# schaltung_endstuffe.net
KiCad netlist of a schematic drawn in EAGLE
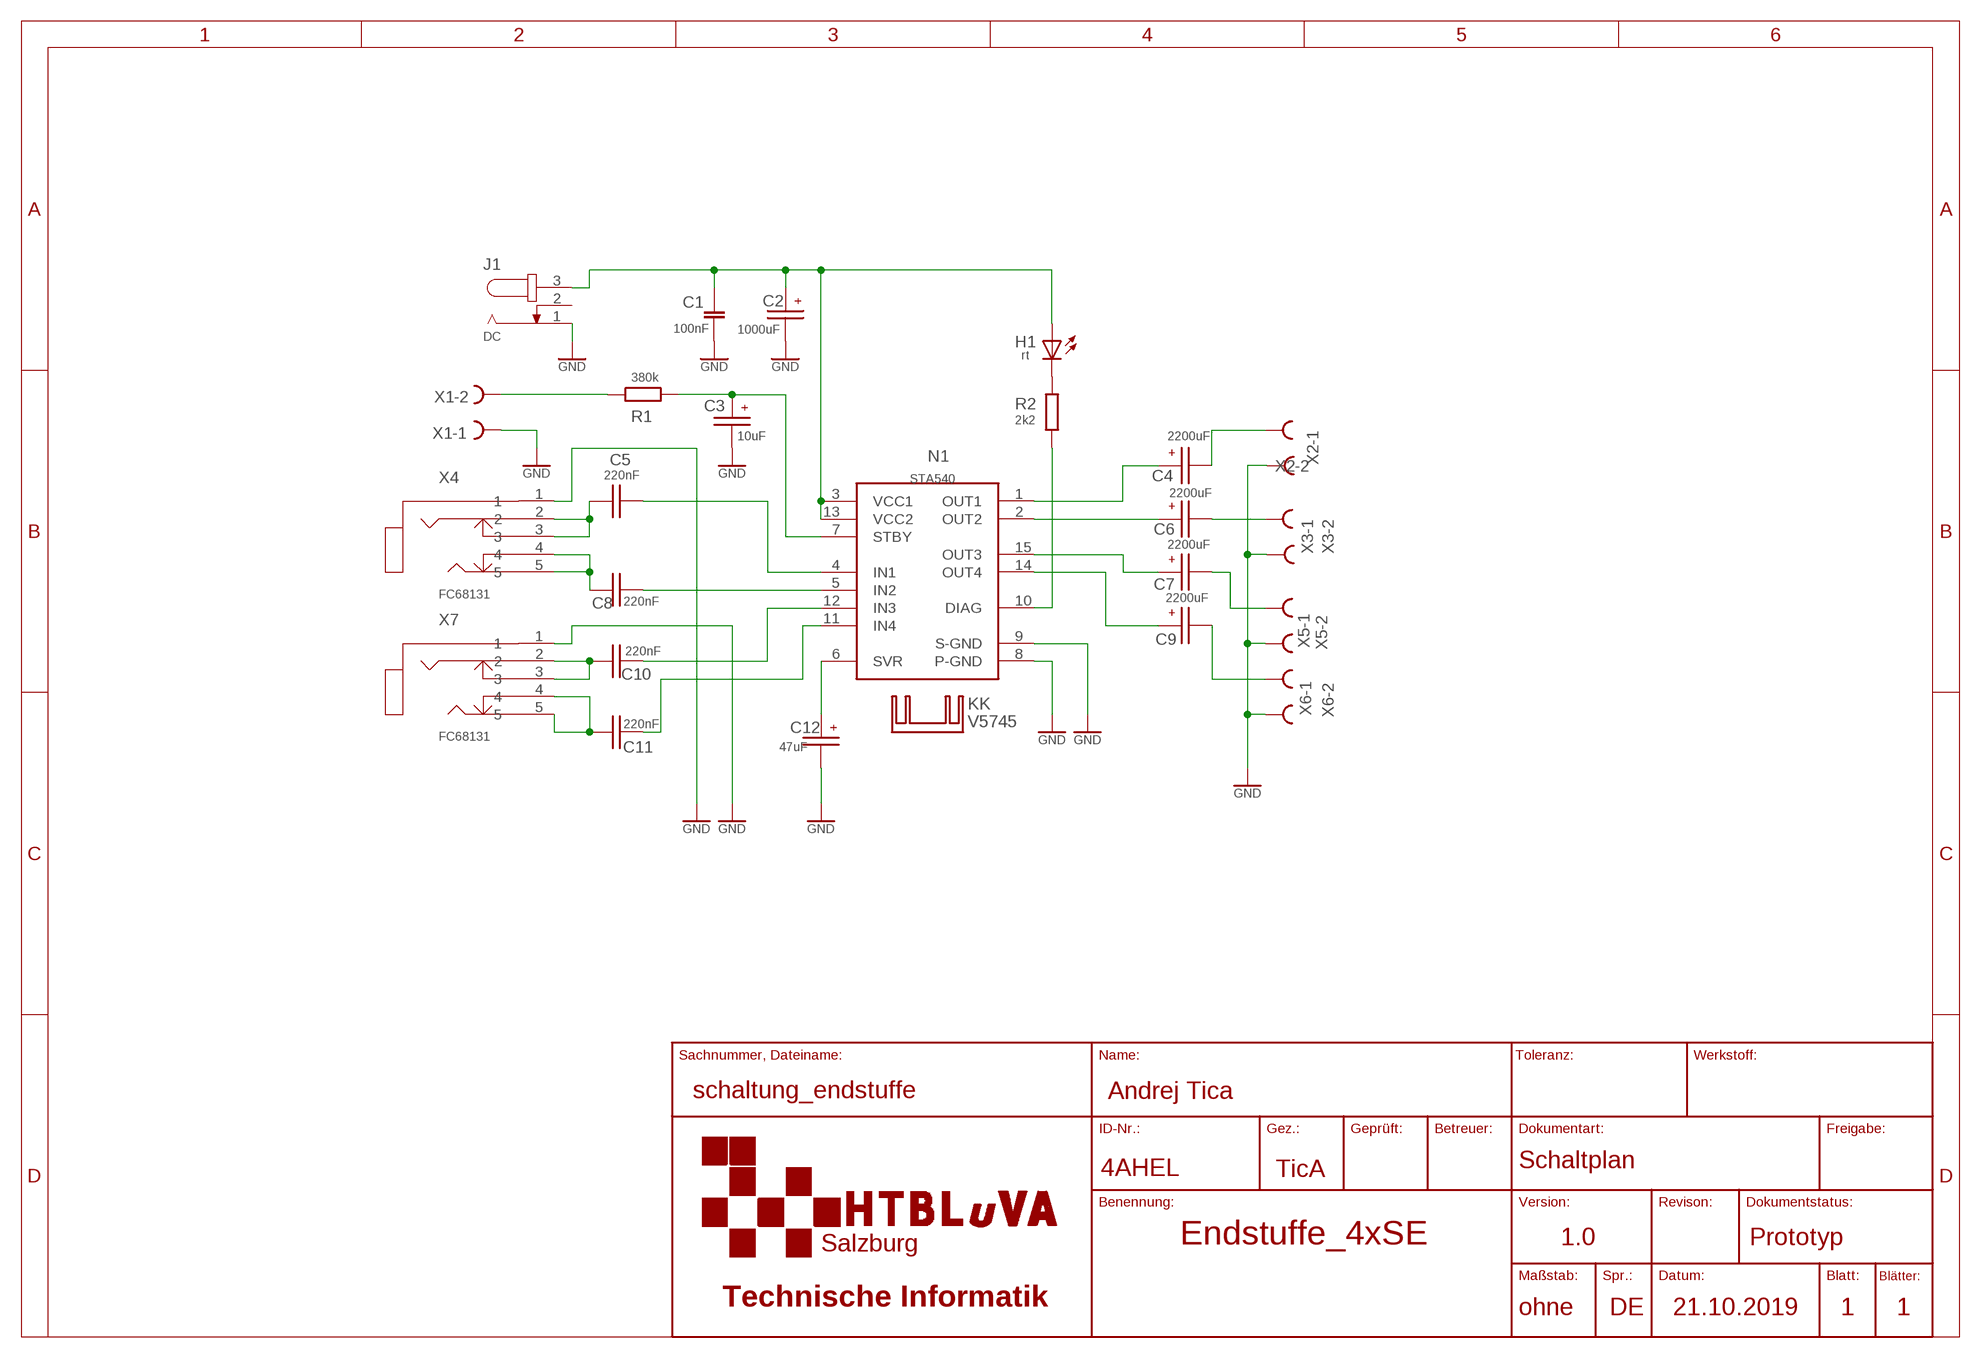
[diagram p0: schematic, sheet 1]

(export (version "E")
  (design (tool "Eeschema 10.0.6"))
  (components
    (comp (ref "C1")
      (value "100nF")
      (footprint "eagle-import:MYLIB_C1206")
      (libsource (lib "eagle-import") (part "C-EU1206"))
    )
    (comp (ref "C2")
      (value "1000uF")
      (footprint "eagle-import:E7,5-16")
      (libsource (lib "eagle-import") (part "CPOL-V_E7.5-16"))
    )
    (comp (ref "C3")
      (value "10uF")
      (footprint "eagle-import:E3,5-8")
      (libsource (lib "eagle-import") (part "CPOL-V_E3.5-8"))
    )
    (comp (ref "C4")
      (value "2200uF")
      (footprint "eagle-import:E7,5-16")
      (libsource (lib "eagle-import") (part "CPOL-V_E7.5-16"))
    )
    (comp (ref "C5")
      (value "220nF")
      (footprint "eagle-import:C050-025X075")
      (libsource (lib "eagle-import") (part "C-V_050-025X075"))
    )
    (comp (ref "C6")
      (value "2200uF")
      (footprint "eagle-import:E7,5-16")
      (libsource (lib "eagle-import") (part "CPOL-V_E7.5-16"))
    )
    (comp (ref "C7")
      (value "2200uF")
      (footprint "eagle-import:E7,5-16")
      (libsource (lib "eagle-import") (part "CPOL-V_E7.5-16"))
    )
    (comp (ref "C8")
      (value "220nF")
      (footprint "eagle-import:C050-025X075")
      (libsource (lib "eagle-import") (part "C-V_050-025X075"))
    )
    (comp (ref "C9")
      (value "2200uF")
      (footprint "eagle-import:E7,5-16")
      (libsource (lib "eagle-import") (part "CPOL-V_E7.5-16"))
    )
    (comp (ref "C10")
      (value "220nF")
      (footprint "eagle-import:C050-025X075")
      (libsource (lib "eagle-import") (part "C-V_050-025X075"))
    )
    (comp (ref "C11")
      (value "220nF")
      (footprint "eagle-import:C050-025X075")
      (libsource (lib "eagle-import") (part "C-V_050-025X075"))
    )
    (comp (ref "C12")
      (value "47uF")
      (footprint "eagle-import:E3,5-8")
      (libsource (lib "eagle-import") (part "CPOL-V_E3.5-8"))
    )
    (comp (ref "H1")
      (value "rt")
      (footprint "eagle-import:LED5MM")
      (libsource (lib "eagle-import") (part "LED_5MM"))
    )
    (comp (ref "J1")
      (value "DC")
      (footprint "eagle-import:SPC4077")
      (libsource (lib "eagle-import") (part "JACK-PLUG0"))
    )
    (comp (ref "KK")
      (value "V5745")
      (footprint "eagle-import:V5745")
      (libsource (lib "eagle-import") (part "V5745"))
    )
    (comp (ref "N1")
      (value "STA540")
      (footprint "eagle-import:MULTIWATT15")
      (fields (field (name "MF") "STMicroelectronics"))
      (libsource (lib "eagle-import") (part "STA540"))
    )
    (comp (ref "R1")
      (value "380k")
      (footprint "eagle-import:0204_7")
      (libsource (lib "eagle-import") (part "R-H_0204/7"))
    )
    (comp (ref "R2")
      (value "2k2")
      (footprint "eagle-import:0204_7")
      (libsource (lib "eagle-import") (part "R-H_0204/7"))
    )
    (comp (ref "X1")
      (value "AK500/2")
      (footprint "eagle-import:AK500_2")
      (libsource (lib "eagle-import") (part "AK500/2"))
    )
    (comp (ref "X2")
      (value "AK500/2")
      (footprint "eagle-import:AK500_2")
      (libsource (lib "eagle-import") (part "AK500/2"))
    )
    (comp (ref "X3")
      (value "AK500/2")
      (footprint "eagle-import:AK500_2")
      (libsource (lib "eagle-import") (part "AK500/2"))
    )
    (comp (ref "X4")
      (value "FC68131")
      (footprint "eagle-import:FC68131-5P")
      (fields (field (name "MF") "Cliff"))
      (libsource (lib "eagle-import") (part "FC68131"))
    )
    (comp (ref "X5")
      (value "AK500/2")
      (footprint "eagle-import:AK500_2")
      (libsource (lib "eagle-import") (part "AK500/2"))
    )
    (comp (ref "X6")
      (value "AK500/2")
      (footprint "eagle-import:AK500_2")
      (libsource (lib "eagle-import") (part "AK500/2"))
    )
    (comp (ref "X7")
      (value "FC68131")
      (footprint "eagle-import:FC68131-5P")
      (fields (field (name "MF") "Cliff"))
      (libsource (lib "eagle-import") (part "FC68131"))
    )
  )
  (nets
    (net (code "1") (name "GND") (class "Default")
      (node (ref "C1") (pin "+") (pinfunction "2_+") (pintype "passive"))
      (node (ref "C12") (pin "-") (pinfunction "-_-") (pintype "passive"))
      (node (ref "C2") (pin "-") (pinfunction "-_-") (pintype "passive"))
      (node (ref "C3") (pin "-") (pinfunction "-_-") (pintype "passive"))
      (node (ref "J1") (pin "1") (pinfunction "1_1") (pintype "passive"))
      (node (ref "N1") (pin "8") (pinfunction "P-GND_8") (pintype "bidirectional"))
      (node (ref "N1") (pin "9") (pinfunction "S-GND_9") (pintype "bidirectional"))
      (node (ref "X1") (pin "1") (pinfunction "KL_1") (pintype "passive"))
      (node (ref "X2") (pin "1") (pinfunction "KL_1") (pintype "passive"))
      (node (ref "X3") (pin "2") (pinfunction "KL_2") (pintype "passive"))
      (node (ref "X4") (pin "1") (pinfunction "1_1") (pintype "bidirectional"))
      (node (ref "X5") (pin "2") (pinfunction "KL_2") (pintype "passive"))
      (node (ref "X6") (pin "2") (pinfunction "KL_2") (pintype "passive"))
      (node (ref "X7") (pin "1") (pinfunction "1_1") (pintype "bidirectional"))
    )
    (net (code "2") (name "Net-(C1-1)") (class "Default")
      (node (ref "C1") (pin "-") (pinfunction "1_-") (pintype "passive"))
      (node (ref "C2") (pin "+") (pinfunction "+_+") (pintype "passive"))
      (node (ref "H1") (pin "A") (pinfunction "A_A") (pintype "passive"))
      (node (ref "J1") (pin "3") (pinfunction "3_3") (pintype "passive"))
      (node (ref "N1") (pin "13") (pinfunction "VCC2_13") (pintype "bidirectional"))
      (node (ref "N1") (pin "3") (pinfunction "VCC1_3") (pintype "bidirectional"))
    )
    (net (code "3") (name "Net-(C5-Pad1)") (class "Default")
      (node (ref "C5") (pin "1") (pinfunction "1_1") (pintype "passive"))
      (node (ref "X4") (pin "2") (pinfunction "2_2") (pintype "bidirectional"))
      (node (ref "X4") (pin "3") (pinfunction "3_3") (pintype "bidirectional"))
    )
    (net (code "4") (name "Net-(C8-Pad1)") (class "Default")
      (node (ref "C8") (pin "1") (pinfunction "1_1") (pintype "passive"))
      (node (ref "X4") (pin "4") (pinfunction "4_4") (pintype "bidirectional"))
      (node (ref "X4") (pin "5") (pinfunction "5_5") (pintype "bidirectional"))
    )
    (net (code "5") (name "Net-(C10-Pad1)") (class "Default")
      (node (ref "C10") (pin "1") (pinfunction "1_1") (pintype "passive"))
      (node (ref "X7") (pin "2") (pinfunction "2_2") (pintype "bidirectional"))
      (node (ref "X7") (pin "3") (pinfunction "3_3") (pintype "bidirectional"))
    )
    (net (code "6") (name "Net-(C11-Pad1)") (class "Default")
      (node (ref "C11") (pin "1") (pinfunction "1_1") (pintype "passive"))
      (node (ref "X7") (pin "4") (pinfunction "4_4") (pintype "bidirectional"))
      (node (ref "X7") (pin "5") (pinfunction "5_5") (pintype "bidirectional"))
    )
    (net (code "7") (name "Net-(H1-C)") (class "Default")
      (node (ref "H1") (pin "K") (pinfunction "C_K") (pintype "passive"))
      (node (ref "R2") (pin "2") (pinfunction "2_2") (pintype "passive"))
    )
    (net (code "8") (name "Net-(N1-DIAG)") (class "Default")
      (node (ref "N1") (pin "10") (pinfunction "DIAG_10") (pintype "bidirectional"))
      (node (ref "R2") (pin "1") (pinfunction "1_1") (pintype "passive"))
    )
    (net (code "9") (name "Net-(N1-IN1)") (class "Default")
      (node (ref "C5") (pin "2") (pinfunction "2_2") (pintype "passive"))
      (node (ref "N1") (pin "4") (pinfunction "IN1_4") (pintype "bidirectional"))
    )
    (net (code "10") (name "Net-(N1-IN2)") (class "Default")
      (node (ref "C8") (pin "2") (pinfunction "2_2") (pintype "passive"))
      (node (ref "N1") (pin "5") (pinfunction "IN2_5") (pintype "bidirectional"))
    )
    (net (code "11") (name "Net-(N1-IN3)") (class "Default")
      (node (ref "C10") (pin "2") (pinfunction "2_2") (pintype "passive"))
      (node (ref "N1") (pin "12") (pinfunction "IN3_12") (pintype "bidirectional"))
    )
    (net (code "12") (name "Net-(N1-IN4)") (class "Default")
      (node (ref "C11") (pin "2") (pinfunction "2_2") (pintype "passive"))
      (node (ref "N1") (pin "11") (pinfunction "IN4_11") (pintype "bidirectional"))
    )
    (net (code "13") (name "Net-(N1-OUT1)") (class "Default")
      (node (ref "C4") (pin "+") (pinfunction "+_+") (pintype "passive"))
      (node (ref "N1") (pin "1") (pinfunction "OUT1_1") (pintype "bidirectional"))
    )
    (net (code "14") (name "Net-(N1-OUT2)") (class "Default")
      (node (ref "C6") (pin "+") (pinfunction "+_+") (pintype "passive"))
      (node (ref "N1") (pin "2") (pinfunction "OUT2_2") (pintype "bidirectional"))
    )
    (net (code "15") (name "Net-(N1-OUT3)") (class "Default")
      (node (ref "C7") (pin "+") (pinfunction "+_+") (pintype "passive"))
      (node (ref "N1") (pin "15") (pinfunction "OUT3_15") (pintype "bidirectional"))
    )
    (net (code "16") (name "Net-(N1-OUT4)") (class "Default")
      (node (ref "C9") (pin "+") (pinfunction "+_+") (pintype "passive"))
      (node (ref "N1") (pin "14") (pinfunction "OUT4_14") (pintype "bidirectional"))
    )
    (net (code "17") (name "Net-(N1-STBY)") (class "Default")
      (node (ref "C3") (pin "+") (pinfunction "+_+") (pintype "passive"))
      (node (ref "N1") (pin "7") (pinfunction "STBY_7") (pintype "bidirectional"))
      (node (ref "R1") (pin "2") (pinfunction "2_2") (pintype "passive"))
    )
    (net (code "18") (name "Net-(N1-SVR)") (class "Default")
      (node (ref "C12") (pin "+") (pinfunction "+_+") (pintype "passive"))
      (node (ref "N1") (pin "6") (pinfunction "SVR_6") (pintype "bidirectional"))
    )
    (net (code "19") (name "Net-(X1B-KL)") (class "Default")
      (node (ref "R1") (pin "1") (pinfunction "1_1") (pintype "passive"))
      (node (ref "X1") (pin "2") (pinfunction "KL_2") (pintype "passive"))
    )
    (net (code "20") (name "Net-(X2B-KL)") (class "Default")
      (node (ref "C4") (pin "-") (pinfunction "-_-") (pintype "passive"))
      (node (ref "X2") (pin "2") (pinfunction "KL_2") (pintype "passive"))
    )
    (net (code "21") (name "Net-(X3A-KL)") (class "Default")
      (node (ref "C6") (pin "-") (pinfunction "-_-") (pintype "passive"))
      (node (ref "X3") (pin "1") (pinfunction "KL_1") (pintype "passive"))
    )
    (net (code "22") (name "Net-(X5A-KL)") (class "Default")
      (node (ref "C7") (pin "-") (pinfunction "-_-") (pintype "passive"))
      (node (ref "X5") (pin "1") (pinfunction "KL_1") (pintype "passive"))
    )
    (net (code "23") (name "Net-(X6A-KL)") (class "Default")
      (node (ref "C9") (pin "-") (pinfunction "-_-") (pintype "passive"))
      (node (ref "X6") (pin "1") (pinfunction "KL_1") (pintype "passive"))
    )
    (net (code "24") (name "unconnected-(J1-Pad2)") (class "Default")
      (node (ref "J1") (pin "2") (pinfunction "2_2") (pintype "passive"))
    )
  )
)
